# Motor_Driver_HIP4082_Board_V1_0.net
KiCad netlist of a schematic drawn in Altium Designer
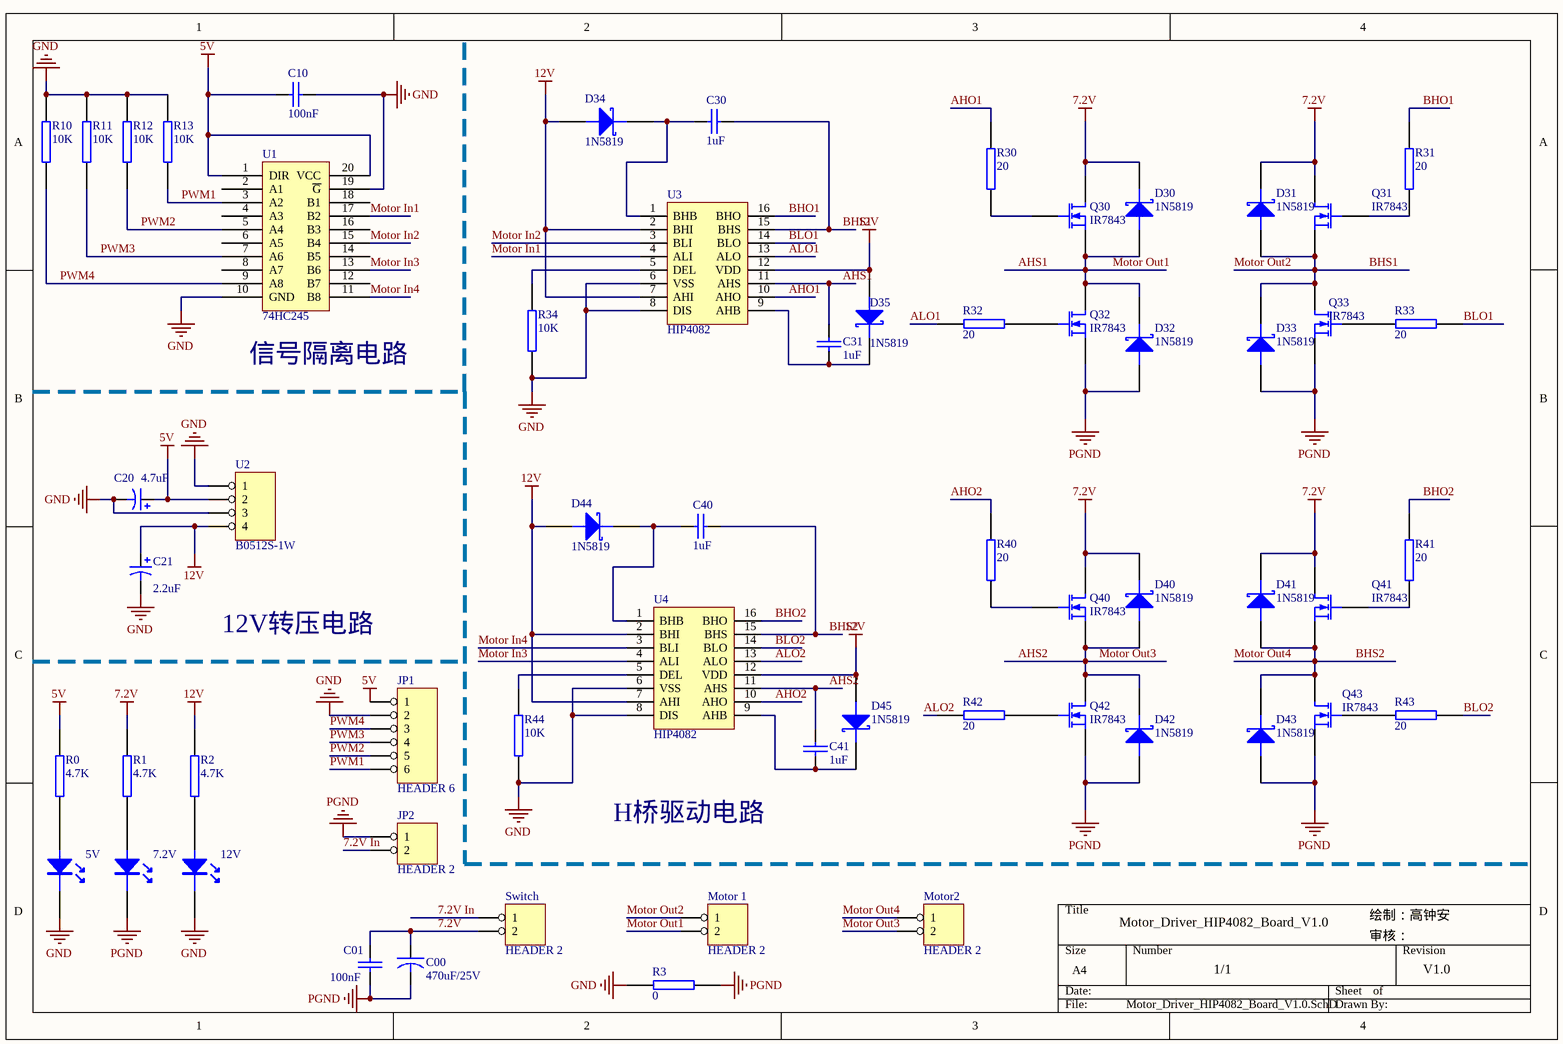
[diagram p0: Motor_Driver_HIP4082_Board_V1.0.SchDoc]

(export (version "E")
  (design (tool "Eeschema 10.0.6"))
  (components
    (comp (ref "5V") (value "~") (footprint "0805_LED_S1") (libsource (lib "Protel99Lib_SCH") (part "LED")))
    (comp (ref "7.2V") (value "~") (footprint "0805_LED_S1") (libsource (lib "Protel99Lib_SCH") (part "LED")))
    (comp (ref "12V") (value "~") (footprint "0805_LED_S1") (libsource (lib "Protel99Lib_SCH") (part "LED")))
    (comp (ref "C00")
      (value "470uF/25V")
      (footprint "RB.2/.4")
      (description "Capacitor")
      (libsource (lib "Protel99Lib_SCH") (part "CAPACITOR"))
    )
    (comp (ref "C01")
      (value "100nF")
      (footprint "0805C")
      (description "Capacitor")
      (libsource (lib "Protel99Lib_SCH") (part "CAP"))
    )
    (comp (ref "C10")
      (value "100nF")
      (footprint "0603_C")
      (description "Capacitor")
      (libsource (lib "Protel99Lib_SCH") (part "CAP"))
    )
    (comp (ref "C20")
      (value "4.7uF")
      (footprint "3528")
      (description "Polarized Capacitor (Surface Mount)")
      (fields (field (name "PUBLISHER") "Altium Limited"))
      (libsource (lib "Miscellaneous Devices") (part "Cap Pol3"))
    )
    (comp (ref "C21")
      (value "2.2uF")
      (footprint "3528")
      (description "Polarized Capacitor (Surface Mount)")
      (fields (field (name "PUBLISHER") "Altium Limited"))
      (libsource (lib "Miscellaneous Devices") (part "Cap Pol3"))
    )
    (comp (ref "C30")
      (value "1uF")
      (footprint "0603C")
      (description "Capacitor")
      (libsource (lib "Protel99Lib_SCH") (part "CAP"))
    )
    (comp (ref "C31")
      (value "1uF")
      (footprint "0603C")
      (description "Capacitor")
      (libsource (lib "Protel99Lib_SCH") (part "CAP"))
    )
    (comp (ref "C40")
      (value "1uF")
      (footprint "0603_C")
      (description "Capacitor")
      (libsource (lib "Protel99Lib_SCH") (part "CAP"))
    )
    (comp (ref "C41")
      (value "1uF")
      (footprint "0603_C")
      (description "Capacitor")
      (libsource (lib "Protel99Lib_SCH") (part "CAP"))
    )
    (comp (ref "D30")
      (value "1N5819")
      (footprint "SOD-323")
      (description "Schottky Diode")
      (libsource (lib "Protel99Lib_SCH") (part "DIODE SCHOTTKY"))
    )
    (comp (ref "D31")
      (value "1N5819")
      (footprint "SOD-323")
      (description "Schottky Diode")
      (libsource (lib "Protel99Lib_SCH") (part "DIODE SCHOTTKY"))
    )
    (comp (ref "D32")
      (value "1N5819")
      (footprint "SOD-323")
      (description "Schottky Diode")
      (libsource (lib "Protel99Lib_SCH") (part "DIODE SCHOTTKY"))
    )
    (comp (ref "D33")
      (value "1N5819")
      (footprint "SOD-323")
      (description "Schottky Diode")
      (libsource (lib "Protel99Lib_SCH") (part "DIODE SCHOTTKY"))
    )
    (comp (ref "D34")
      (value "1N5819")
      (footprint "SOD-323")
      (description "Schottky Diode")
      (libsource (lib "Protel99Lib_SCH") (part "DIODE SCHOTTKY"))
    )
    (comp (ref "D35")
      (value "1N5819")
      (footprint "SOD-323")
      (description "Schottky Diode")
      (libsource (lib "Protel99Lib_SCH") (part "DIODE SCHOTTKY"))
    )
    (comp (ref "D40")
      (value "1N5819")
      (footprint "SOD-323")
      (description "Schottky Diode")
      (libsource (lib "Protel99Lib_SCH") (part "DIODE SCHOTTKY"))
    )
    (comp (ref "D41")
      (value "1N5819")
      (footprint "SOD-323")
      (description "Schottky Diode")
      (libsource (lib "Protel99Lib_SCH") (part "DIODE SCHOTTKY"))
    )
    (comp (ref "D42")
      (value "1N5819")
      (footprint "SOD-323")
      (description "Schottky Diode")
      (libsource (lib "Protel99Lib_SCH") (part "DIODE SCHOTTKY"))
    )
    (comp (ref "D43")
      (value "1N5819")
      (footprint "SOD-323")
      (description "Schottky Diode")
      (libsource (lib "Protel99Lib_SCH") (part "DIODE SCHOTTKY"))
    )
    (comp (ref "D44")
      (value "1N5819")
      (footprint "SOD-323")
      (description "Schottky Diode")
      (libsource (lib "Protel99Lib_SCH") (part "DIODE SCHOTTKY"))
    )
    (comp (ref "D45")
      (value "1N5819")
      (footprint "SOD-323")
      (description "Schottky Diode")
      (libsource (lib "Protel99Lib_SCH") (part "DIODE SCHOTTKY"))
    )
    (comp (ref "JP1")
      (value "HEADER 6")
      (footprint "SIP6N")
      (libsource (lib "Protel99Lib_SCH") (part "HEADER 6"))
    )
    (comp (ref "JP2")
      (value "HEADER 2")
      (footprint "KF301-2P")
      (libsource (lib "Protel99Lib_SCH") (part "HEADER 2"))
    )
    (comp (ref "Motor 1")
      (value "HEADER 2")
      (footprint "KF301-2P")
      (libsource (lib "Protel99Lib_SCH") (part "HEADER 2"))
    )
    (comp (ref "Motor2")
      (value "HEADER 2")
      (footprint "KF301-2P")
      (libsource (lib "Protel99Lib_SCH") (part "HEADER 2"))
    )
    (comp (ref "Q30")
      (value "IR7843")
      (footprint "LR7843")
      (description "N-Channel MOSFET")
      (fields (field (name "PUBLISHER") "Altium Limited"))
      (libsource (lib "Miscellaneous Devices") (part "MOSFET-N"))
    )
    (comp (ref "Q31")
      (value "IR7843")
      (footprint "LR7843")
      (description "N-Channel MOSFET")
      (fields (field (name "PUBLISHER") "Altium Limited"))
      (libsource (lib "Miscellaneous Devices") (part "MOSFET-N"))
    )
    (comp (ref "Q32")
      (value "IR7843")
      (footprint "LR7843")
      (description "N-Channel MOSFET")
      (fields (field (name "PUBLISHER") "Altium Limited"))
      (libsource (lib "Miscellaneous Devices") (part "MOSFET-N"))
    )
    (comp (ref "Q33")
      (value "IR7843")
      (footprint "LR7843")
      (description "N-Channel MOSFET")
      (fields (field (name "PUBLISHER") "Altium Limited"))
      (libsource (lib "Miscellaneous Devices") (part "MOSFET-N"))
    )
    (comp (ref "Q40")
      (value "IR7843")
      (footprint "LR7843")
      (description "N-Channel MOSFET")
      (fields (field (name "PUBLISHER") "Altium Limited"))
      (libsource (lib "Miscellaneous Devices") (part "MOSFET-N"))
    )
    (comp (ref "Q41")
      (value "IR7843")
      (footprint "LR7843")
      (description "N-Channel MOSFET")
      (fields (field (name "PUBLISHER") "Altium Limited"))
      (libsource (lib "Miscellaneous Devices") (part "MOSFET-N"))
    )
    (comp (ref "Q42")
      (value "IR7843")
      (footprint "LR7843")
      (description "N-Channel MOSFET")
      (fields (field (name "PUBLISHER") "Altium Limited"))
      (libsource (lib "Miscellaneous Devices") (part "MOSFET-N"))
    )
    (comp (ref "Q43")
      (value "IR7843")
      (footprint "LR7843")
      (description "N-Channel MOSFET")
      (fields (field (name "PUBLISHER") "Altium Limited"))
      (libsource (lib "Miscellaneous Devices") (part "MOSFET-N"))
    )
    (comp (ref "R0") (value "4.7K") (footprint "0603_R") (libsource (lib "Protel99Lib_SCH") (part "RES2")))
    (comp (ref "R1") (value "4.7K") (footprint "0603_R") (libsource (lib "Protel99Lib_SCH") (part "RES2")))
    (comp (ref "R2") (value "4.7K") (footprint "0603_R") (libsource (lib "Protel99Lib_SCH") (part "RES2")))
    (comp (ref "R3") (value "0") (footprint "0805") (libsource (lib "Protel99Lib_SCH") (part "RES2")))
    (comp (ref "R10") (value "10K") (footprint "0603_R") (libsource (lib "") (part "RES2_1")))
    (comp (ref "R11") (value "10K") (footprint "0603_R") (libsource (lib "") (part "RES2_1")))
    (comp (ref "R12") (value "10K") (footprint "0603_R") (libsource (lib "") (part "RES2_1")))
    (comp (ref "R13") (value "10K") (footprint "0603_R") (libsource (lib "") (part "RES2_1")))
    (comp (ref "R30") (value "20") (footprint "0805") (libsource (lib "Protel99Lib_SCH") (part "RES2")))
    (comp (ref "R31") (value "20") (footprint "0805") (libsource (lib "Protel99Lib_SCH") (part "RES2")))
    (comp (ref "R32") (value "20") (footprint "0805") (libsource (lib "Protel99Lib_SCH") (part "RES2")))
    (comp (ref "R33") (value "20") (footprint "0805") (libsource (lib "Protel99Lib_SCH") (part "RES2")))
    (comp (ref "R34") (value "10K") (footprint "0603_R") (libsource (lib "Protel99Lib_SCH") (part "RES2")))
    (comp (ref "R40") (value "20") (footprint "0805") (libsource (lib "Protel99Lib_SCH") (part "RES2")))
    (comp (ref "R41") (value "20") (footprint "0805") (libsource (lib "Protel99Lib_SCH") (part "RES2")))
    (comp (ref "R42") (value "20") (footprint "0805") (libsource (lib "Protel99Lib_SCH") (part "RES2")))
    (comp (ref "R43") (value "20") (footprint "0805") (libsource (lib "Protel99Lib_SCH") (part "RES2")))
    (comp (ref "R44") (value "10K") (footprint "0603_R") (libsource (lib "Protel99Lib_SCH") (part "RES2")))
    (comp (ref "Switch")
      (value "HEADER 2")
      (footprint "SWITCH-MINI")
      (libsource (lib "Protel99Lib_SCH") (part "HEADER 2"))
    )
    (comp (ref "U1") (value "74HC245") (footprint "SOP20") (libsource (lib "BaseLib_SCH") (part "74HC245")))
    (comp (ref "U2")
      (value "B0512S-1W")
      (footprint "SIP4_B_S-1W")
      (description "4 Pin Header")
      (libsource (lib "Protel99Lib_SCH") (part "4 HEADER"))
    )
    (comp (ref "U3")
      (value "HIP4082")
      (footprint "SOP-16_208mil")
      (libsource (lib "Motor_Driver_HIP4082_Board_V1.0") (part "HIP4082"))
    )
    (comp (ref "U4")
      (value "HIP4082")
      (footprint "SOP-16_208mil")
      (libsource (lib "Motor_Driver_HIP4082_Board_V1.0") (part "HIP4082"))
    )
  )
  (nets
    (net (code "1") (name "/7.2V In") (class "Default")
      (node (ref "JP2") (pin "2") (pinfunction "2_2") (pintype "passive"))
      (node (ref "Switch") (pin "1") (pinfunction "1_1") (pintype "passive"))
    )
    (net (code "2") (name "/AHO1") (class "Default")
      (node (ref "R30") (pin "2") (pinfunction "2_2") (pintype "passive"))
      (node (ref "U3") (pin "10") (pinfunction "AHO_10") (pintype "passive"))
    )
    (net (code "3") (name "/AHO2") (class "Default")
      (node (ref "R40") (pin "2") (pinfunction "2_2") (pintype "passive"))
      (node (ref "U4") (pin "10") (pinfunction "AHO_10") (pintype "passive"))
    )
    (net (code "4") (name "/AHS1") (class "Default")
      (node (ref "C31") (pin "2") (pinfunction "2_2") (pintype "passive"))
      (node (ref "D30") (pin "1") (pinfunction "A_1") (pintype "passive"))
      (node (ref "D32") (pin "2") (pinfunction "K_2") (pintype "passive"))
      (node (ref "Motor 1") (pin "2") (pinfunction "2_2") (pintype "passive"))
      (node (ref "Q30") (pin "3") (pinfunction "S_3") (pintype "passive"))
      (node (ref "Q32") (pin "1") (pinfunction "D_1") (pintype "passive"))
      (node (ref "U3") (pin "11") (pinfunction "AHS_11") (pintype "passive"))
    )
    (net (code "5") (name "/AHS2") (class "Default")
      (node (ref "C41") (pin "2") (pinfunction "2_2") (pintype "passive"))
      (node (ref "D40") (pin "1") (pinfunction "A_1") (pintype "passive"))
      (node (ref "D42") (pin "2") (pinfunction "K_2") (pintype "passive"))
      (node (ref "Motor2") (pin "2") (pinfunction "2_2") (pintype "passive"))
      (node (ref "Q40") (pin "3") (pinfunction "S_3") (pintype "passive"))
      (node (ref "Q42") (pin "1") (pinfunction "D_1") (pintype "passive"))
      (node (ref "U4") (pin "11") (pinfunction "AHS_11") (pintype "passive"))
    )
    (net (code "6") (name "/ALO1") (class "Default")
      (node (ref "R32") (pin "2") (pinfunction "2_2") (pintype "passive"))
      (node (ref "U3") (pin "13") (pinfunction "ALO_13") (pintype "passive"))
    )
    (net (code "7") (name "/ALO2") (class "Default")
      (node (ref "R42") (pin "2") (pinfunction "2_2") (pintype "passive"))
      (node (ref "U4") (pin "13") (pinfunction "ALO_13") (pintype "passive"))
    )
    (net (code "8") (name "/BHO1") (class "Default")
      (node (ref "R31") (pin "2") (pinfunction "2_2") (pintype "passive"))
      (node (ref "U3") (pin "16") (pinfunction "BHO_16") (pintype "passive"))
    )
    (net (code "9") (name "/BHO2") (class "Default")
      (node (ref "R41") (pin "2") (pinfunction "2_2") (pintype "passive"))
      (node (ref "U4") (pin "16") (pinfunction "BHO_16") (pintype "passive"))
    )
    (net (code "10") (name "/BHS1") (class "Default")
      (node (ref "C30") (pin "2") (pinfunction "2_2") (pintype "passive"))
      (node (ref "D31") (pin "1") (pinfunction "A_1") (pintype "passive"))
      (node (ref "D33") (pin "2") (pinfunction "K_2") (pintype "passive"))
      (node (ref "Motor 1") (pin "1") (pinfunction "1_1") (pintype "passive"))
      (node (ref "Q31") (pin "3") (pinfunction "S_3") (pintype "passive"))
      (node (ref "Q33") (pin "1") (pinfunction "D_1") (pintype "passive"))
      (node (ref "U3") (pin "15") (pinfunction "BHS_15") (pintype "passive"))
    )
    (net (code "11") (name "/BHS2") (class "Default")
      (node (ref "C40") (pin "2") (pinfunction "2_2") (pintype "passive"))
      (node (ref "D41") (pin "1") (pinfunction "A_1") (pintype "passive"))
      (node (ref "D43") (pin "2") (pinfunction "K_2") (pintype "passive"))
      (node (ref "Motor2") (pin "1") (pinfunction "1_1") (pintype "passive"))
      (node (ref "Q41") (pin "3") (pinfunction "S_3") (pintype "passive"))
      (node (ref "Q43") (pin "1") (pinfunction "D_1") (pintype "passive"))
      (node (ref "U4") (pin "15") (pinfunction "BHS_15") (pintype "passive"))
    )
    (net (code "12") (name "/BLO1") (class "Default")
      (node (ref "R33") (pin "1") (pinfunction "1_1") (pintype "passive"))
      (node (ref "U3") (pin "14") (pinfunction "BLO_14") (pintype "passive"))
    )
    (net (code "13") (name "/BLO2") (class "Default")
      (node (ref "R43") (pin "1") (pinfunction "1_1") (pintype "passive"))
      (node (ref "U4") (pin "14") (pinfunction "BLO_14") (pintype "passive"))
    )
    (net (code "14") (name "/Motor In1") (class "Default")
      (node (ref "U1") (pin "17") (pinfunction "B2_17") (pintype "passive"))
      (node (ref "U3") (pin "4") (pinfunction "ALI_4") (pintype "passive"))
    )
    (net (code "15") (name "/Motor In2") (class "Default")
      (node (ref "U1") (pin "15") (pinfunction "B4_15") (pintype "passive"))
      (node (ref "U3") (pin "3") (pinfunction "BLI_3") (pintype "passive"))
    )
    (net (code "16") (name "/Motor In3") (class "Default")
      (node (ref "U1") (pin "13") (pinfunction "B6_13") (pintype "passive"))
      (node (ref "U4") (pin "4") (pinfunction "ALI_4") (pintype "passive"))
    )
    (net (code "17") (name "/Motor In4") (class "Default")
      (node (ref "U1") (pin "11") (pinfunction "B8_11") (pintype "passive"))
      (node (ref "U4") (pin "3") (pinfunction "BLI_3") (pintype "passive"))
    )
    (net (code "18") (name "/PWM1") (class "Default")
      (node (ref "JP1") (pin "6") (pinfunction "6_6") (pintype "passive"))
      (node (ref "R13") (pin "1") (pinfunction "1_1") (pintype "passive"))
      (node (ref "U1") (pin "3") (pinfunction "A2_3") (pintype "passive"))
    )
    (net (code "19") (name "/PWM2") (class "Default")
      (node (ref "JP1") (pin "5") (pinfunction "5_5") (pintype "passive"))
      (node (ref "R12") (pin "1") (pinfunction "1_1") (pintype "passive"))
      (node (ref "U1") (pin "5") (pinfunction "A4_5") (pintype "passive"))
    )
    (net (code "20") (name "/PWM3") (class "Default")
      (node (ref "JP1") (pin "4") (pinfunction "4_4") (pintype "passive"))
      (node (ref "R11") (pin "2") (pinfunction "2_2") (pintype "passive"))
      (node (ref "U1") (pin "7") (pinfunction "A6_7") (pintype "passive"))
    )
    (net (code "21") (name "/PWM4") (class "Default")
      (node (ref "JP1") (pin "3") (pinfunction "3_3") (pintype "passive"))
      (node (ref "R10") (pin "1") (pinfunction "1_1") (pintype "passive"))
      (node (ref "U1") (pin "9") (pinfunction "A8_9") (pintype "passive"))
    )
    (net (code "22") (name "5V") (class "Default")
      (node (ref "C10") (pin "1") (pinfunction "1_1") (pintype "passive"))
      (node (ref "C20") (pin "1") (pinfunction "1_1") (pintype "passive"))
      (node (ref "JP1") (pin "1") (pinfunction "1_1") (pintype "passive"))
      (node (ref "R0") (pin "2") (pinfunction "2_2") (pintype "passive"))
      (node (ref "U1") (pin "1") (pinfunction "DIR_1") (pintype "passive"))
      (node (ref "U1") (pin "20") (pinfunction "VCC_20") (pintype "passive"))
      (node (ref "U2") (pin "2") (pinfunction "2_2") (pintype "passive"))
    )
    (net (code "23") (name "7.2V") (class "Default")
      (node (ref "C00") (pin "1") (pinfunction "1_1") (pintype "passive"))
      (node (ref "C01") (pin "2") (pinfunction "2_2") (pintype "passive"))
      (node (ref "D30") (pin "2") (pinfunction "K_2") (pintype "passive"))
      (node (ref "D31") (pin "2") (pinfunction "K_2") (pintype "passive"))
      (node (ref "D40") (pin "2") (pinfunction "K_2") (pintype "passive"))
      (node (ref "D41") (pin "2") (pinfunction "K_2") (pintype "passive"))
      (node (ref "Q30") (pin "1") (pinfunction "D_1") (pintype "passive"))
      (node (ref "Q31") (pin "1") (pinfunction "D_1") (pintype "passive"))
      (node (ref "Q40") (pin "1") (pinfunction "D_1") (pintype "passive"))
      (node (ref "Q41") (pin "1") (pinfunction "D_1") (pintype "passive"))
      (node (ref "R1") (pin "2") (pinfunction "2_2") (pintype "passive"))
      (node (ref "Switch") (pin "2") (pinfunction "2_2") (pintype "passive"))
    )
    (net (code "24") (name "12V") (class "Default")
      (node (ref "C21") (pin "1") (pinfunction "1_1") (pintype "passive"))
      (node (ref "D34") (pin "1") (pinfunction "A_1") (pintype "passive"))
      (node (ref "D35") (pin "1") (pinfunction "A_1") (pintype "passive"))
      (node (ref "D44") (pin "1") (pinfunction "A_1") (pintype "passive"))
      (node (ref "D45") (pin "1") (pinfunction "A_1") (pintype "passive"))
      (node (ref "R2") (pin "2") (pinfunction "2_2") (pintype "passive"))
      (node (ref "U2") (pin "4") (pinfunction "4_4") (pintype "passive"))
      (node (ref "U3") (pin "12") (pinfunction "VDD_12") (pintype "passive"))
      (node (ref "U3") (pin "2") (pinfunction "BHI_2") (pintype "passive"))
      (node (ref "U3") (pin "7") (pinfunction "AHI_7") (pintype "passive"))
      (node (ref "U4") (pin "12") (pinfunction "VDD_12") (pintype "passive"))
      (node (ref "U4") (pin "2") (pinfunction "BHI_2") (pintype "passive"))
      (node (ref "U4") (pin "7") (pinfunction "AHI_7") (pintype "passive"))
    )
    (net (code "25") (name "GND") (class "Default")
      (node (ref "12V") (pin "K") (pinfunction "2_K") (pintype "passive"))
      (node (ref "5V") (pin "K") (pinfunction "2_K") (pintype "passive"))
      (node (ref "C10") (pin "2") (pinfunction "2_2") (pintype "passive"))
      (node (ref "C20") (pin "2") (pinfunction "2_2") (pintype "passive"))
      (node (ref "C21") (pin "2") (pinfunction "2_2") (pintype "passive"))
      (node (ref "JP1") (pin "2") (pinfunction "2_2") (pintype "passive"))
      (node (ref "R10") (pin "2") (pinfunction "2_2") (pintype "passive"))
      (node (ref "R11") (pin "1") (pinfunction "1_1") (pintype "passive"))
      (node (ref "R12") (pin "2") (pinfunction "2_2") (pintype "passive"))
      (node (ref "R13") (pin "2") (pinfunction "2_2") (pintype "passive"))
      (node (ref "R3") (pin "2") (pinfunction "2_2") (pintype "passive"))
      (node (ref "R34") (pin "1") (pinfunction "1_1") (pintype "passive"))
      (node (ref "R44") (pin "1") (pinfunction "1_1") (pintype "passive"))
      (node (ref "U1") (pin "10") (pinfunction "GND_10") (pintype "passive"))
      (node (ref "U1") (pin "19") (pinfunction "~{G}_19") (pintype "passive"))
      (node (ref "U2") (pin "1") (pinfunction "1_1") (pintype "passive"))
      (node (ref "U2") (pin "3") (pinfunction "3_3") (pintype "passive"))
      (node (ref "U3") (pin "6") (pinfunction "VSS_6") (pintype "passive"))
      (node (ref "U3") (pin "8") (pinfunction "DIS_8") (pintype "passive"))
      (node (ref "U4") (pin "6") (pinfunction "VSS_6") (pintype "passive"))
      (node (ref "U4") (pin "8") (pinfunction "DIS_8") (pintype "passive"))
    )
    (net (code "26") (name "Net-(5V-1)") (class "Default")
      (node (ref "5V") (pin "A") (pinfunction "1_A") (pintype "passive"))
      (node (ref "R0") (pin "1") (pinfunction "1_1") (pintype "passive"))
    )
    (net (code "27") (name "Net-(7.2V-1)") (class "Default")
      (node (ref "7.2V") (pin "A") (pinfunction "1_A") (pintype "passive"))
      (node (ref "R1") (pin "1") (pinfunction "1_1") (pintype "passive"))
    )
    (net (code "28") (name "Net-(12V-1)") (class "Default")
      (node (ref "12V") (pin "A") (pinfunction "1_A") (pintype "passive"))
      (node (ref "R2") (pin "1") (pinfunction "1_1") (pintype "passive"))
    )
    (net (code "29") (name "Net-(D34-K)") (class "Default")
      (node (ref "C30") (pin "1") (pinfunction "1_1") (pintype "passive"))
      (node (ref "D34") (pin "2") (pinfunction "K_2") (pintype "passive"))
      (node (ref "U3") (pin "1") (pinfunction "BHB_1") (pintype "passive"))
    )
    (net (code "30") (name "Net-(D35-K)") (class "Default")
      (node (ref "C31") (pin "1") (pinfunction "1_1") (pintype "passive"))
      (node (ref "D35") (pin "2") (pinfunction "K_2") (pintype "passive"))
      (node (ref "U3") (pin "9") (pinfunction "AHB_9") (pintype "passive"))
    )
    (net (code "31") (name "Net-(D44-K)") (class "Default")
      (node (ref "C40") (pin "1") (pinfunction "1_1") (pintype "passive"))
      (node (ref "D44") (pin "2") (pinfunction "K_2") (pintype "passive"))
      (node (ref "U4") (pin "1") (pinfunction "BHB_1") (pintype "passive"))
    )
    (net (code "32") (name "Net-(D45-K)") (class "Default")
      (node (ref "C41") (pin "1") (pinfunction "1_1") (pintype "passive"))
      (node (ref "D45") (pin "2") (pinfunction "K_2") (pintype "passive"))
      (node (ref "U4") (pin "9") (pinfunction "AHB_9") (pintype "passive"))
    )
    (net (code "33") (name "Net-(Q30-G)") (class "Default")
      (node (ref "Q30") (pin "2") (pinfunction "G_2") (pintype "passive"))
      (node (ref "R30") (pin "1") (pinfunction "1_1") (pintype "passive"))
    )
    (net (code "34") (name "Net-(Q31-G)") (class "Default")
      (node (ref "Q31") (pin "2") (pinfunction "G_2") (pintype "passive"))
      (node (ref "R31") (pin "1") (pinfunction "1_1") (pintype "passive"))
    )
    (net (code "35") (name "Net-(Q32-G)") (class "Default")
      (node (ref "Q32") (pin "2") (pinfunction "G_2") (pintype "passive"))
      (node (ref "R32") (pin "1") (pinfunction "1_1") (pintype "passive"))
    )
    (net (code "36") (name "Net-(Q33-G)") (class "Default")
      (node (ref "Q33") (pin "2") (pinfunction "G_2") (pintype "passive"))
      (node (ref "R33") (pin "2") (pinfunction "2_2") (pintype "passive"))
    )
    (net (code "37") (name "Net-(Q40-G)") (class "Default")
      (node (ref "Q40") (pin "2") (pinfunction "G_2") (pintype "passive"))
      (node (ref "R40") (pin "1") (pinfunction "1_1") (pintype "passive"))
    )
    (net (code "38") (name "Net-(Q41-G)") (class "Default")
      (node (ref "Q41") (pin "2") (pinfunction "G_2") (pintype "passive"))
      (node (ref "R41") (pin "1") (pinfunction "1_1") (pintype "passive"))
    )
    (net (code "39") (name "Net-(Q42-G)") (class "Default")
      (node (ref "Q42") (pin "2") (pinfunction "G_2") (pintype "passive"))
      (node (ref "R42") (pin "1") (pinfunction "1_1") (pintype "passive"))
    )
    (net (code "40") (name "Net-(Q43-G)") (class "Default")
      (node (ref "Q43") (pin "2") (pinfunction "G_2") (pintype "passive"))
      (node (ref "R43") (pin "2") (pinfunction "2_2") (pintype "passive"))
    )
    (net (code "41") (name "Net-(U3-DEL)") (class "Default")
      (node (ref "R34") (pin "2") (pinfunction "2_2") (pintype "passive"))
      (node (ref "U3") (pin "5") (pinfunction "DEL_5") (pintype "passive"))
    )
    (net (code "42") (name "Net-(U4-DEL)") (class "Default")
      (node (ref "R44") (pin "2") (pinfunction "2_2") (pintype "passive"))
      (node (ref "U4") (pin "5") (pinfunction "DEL_5") (pintype "passive"))
    )
    (net (code "43") (name "PGND") (class "Default")
      (node (ref "7.2V") (pin "K") (pinfunction "2_K") (pintype "passive"))
      (node (ref "C00") (pin "2") (pinfunction "2_2") (pintype "passive"))
      (node (ref "C01") (pin "1") (pinfunction "1_1") (pintype "passive"))
      (node (ref "D32") (pin "1") (pinfunction "A_1") (pintype "passive"))
      (node (ref "D33") (pin "1") (pinfunction "A_1") (pintype "passive"))
      (node (ref "D42") (pin "1") (pinfunction "A_1") (pintype "passive"))
      (node (ref "D43") (pin "1") (pinfunction "A_1") (pintype "passive"))
      (node (ref "JP2") (pin "1") (pinfunction "1_1") (pintype "passive"))
      (node (ref "Q32") (pin "3") (pinfunction "S_3") (pintype "passive"))
      (node (ref "Q33") (pin "3") (pinfunction "S_3") (pintype "passive"))
      (node (ref "Q42") (pin "3") (pinfunction "S_3") (pintype "passive"))
      (node (ref "Q43") (pin "3") (pinfunction "S_3") (pintype "passive"))
      (node (ref "R3") (pin "1") (pinfunction "1_1") (pintype "passive"))
    )
    (net (code "44") (name "unconnected-(U1-A1-Pad2)") (class "Default")
      (node (ref "U1") (pin "2") (pinfunction "A1_2") (pintype "passive"))
    )
    (net (code "45") (name "unconnected-(U1-A3-Pad4)") (class "Default")
      (node (ref "U1") (pin "4") (pinfunction "A3_4") (pintype "passive"))
    )
    (net (code "46") (name "unconnected-(U1-A5-Pad6)") (class "Default")
      (node (ref "U1") (pin "6") (pinfunction "A5_6") (pintype "passive"))
    )
    (net (code "47") (name "unconnected-(U1-A7-Pad8)") (class "Default")
      (node (ref "U1") (pin "8") (pinfunction "A7_8") (pintype "passive"))
    )
    (net (code "48") (name "unconnected-(U1-B1-Pad18)") (class "Default")
      (node (ref "U1") (pin "18") (pinfunction "B1_18") (pintype "passive"))
    )
    (net (code "49") (name "unconnected-(U1-B3-Pad16)") (class "Default")
      (node (ref "U1") (pin "16") (pinfunction "B3_16") (pintype "passive"))
    )
    (net (code "50") (name "unconnected-(U1-B5-Pad14)") (class "Default")
      (node (ref "U1") (pin "14") (pinfunction "B5_14") (pintype "passive"))
    )
    (net (code "51") (name "unconnected-(U1-B7-Pad12)") (class "Default")
      (node (ref "U1") (pin "12") (pinfunction "B7_12") (pintype "passive"))
    )
  )
)
